# 1-Schematic_proiect.net
KiCad netlist of a schematic drawn in EasyEDA
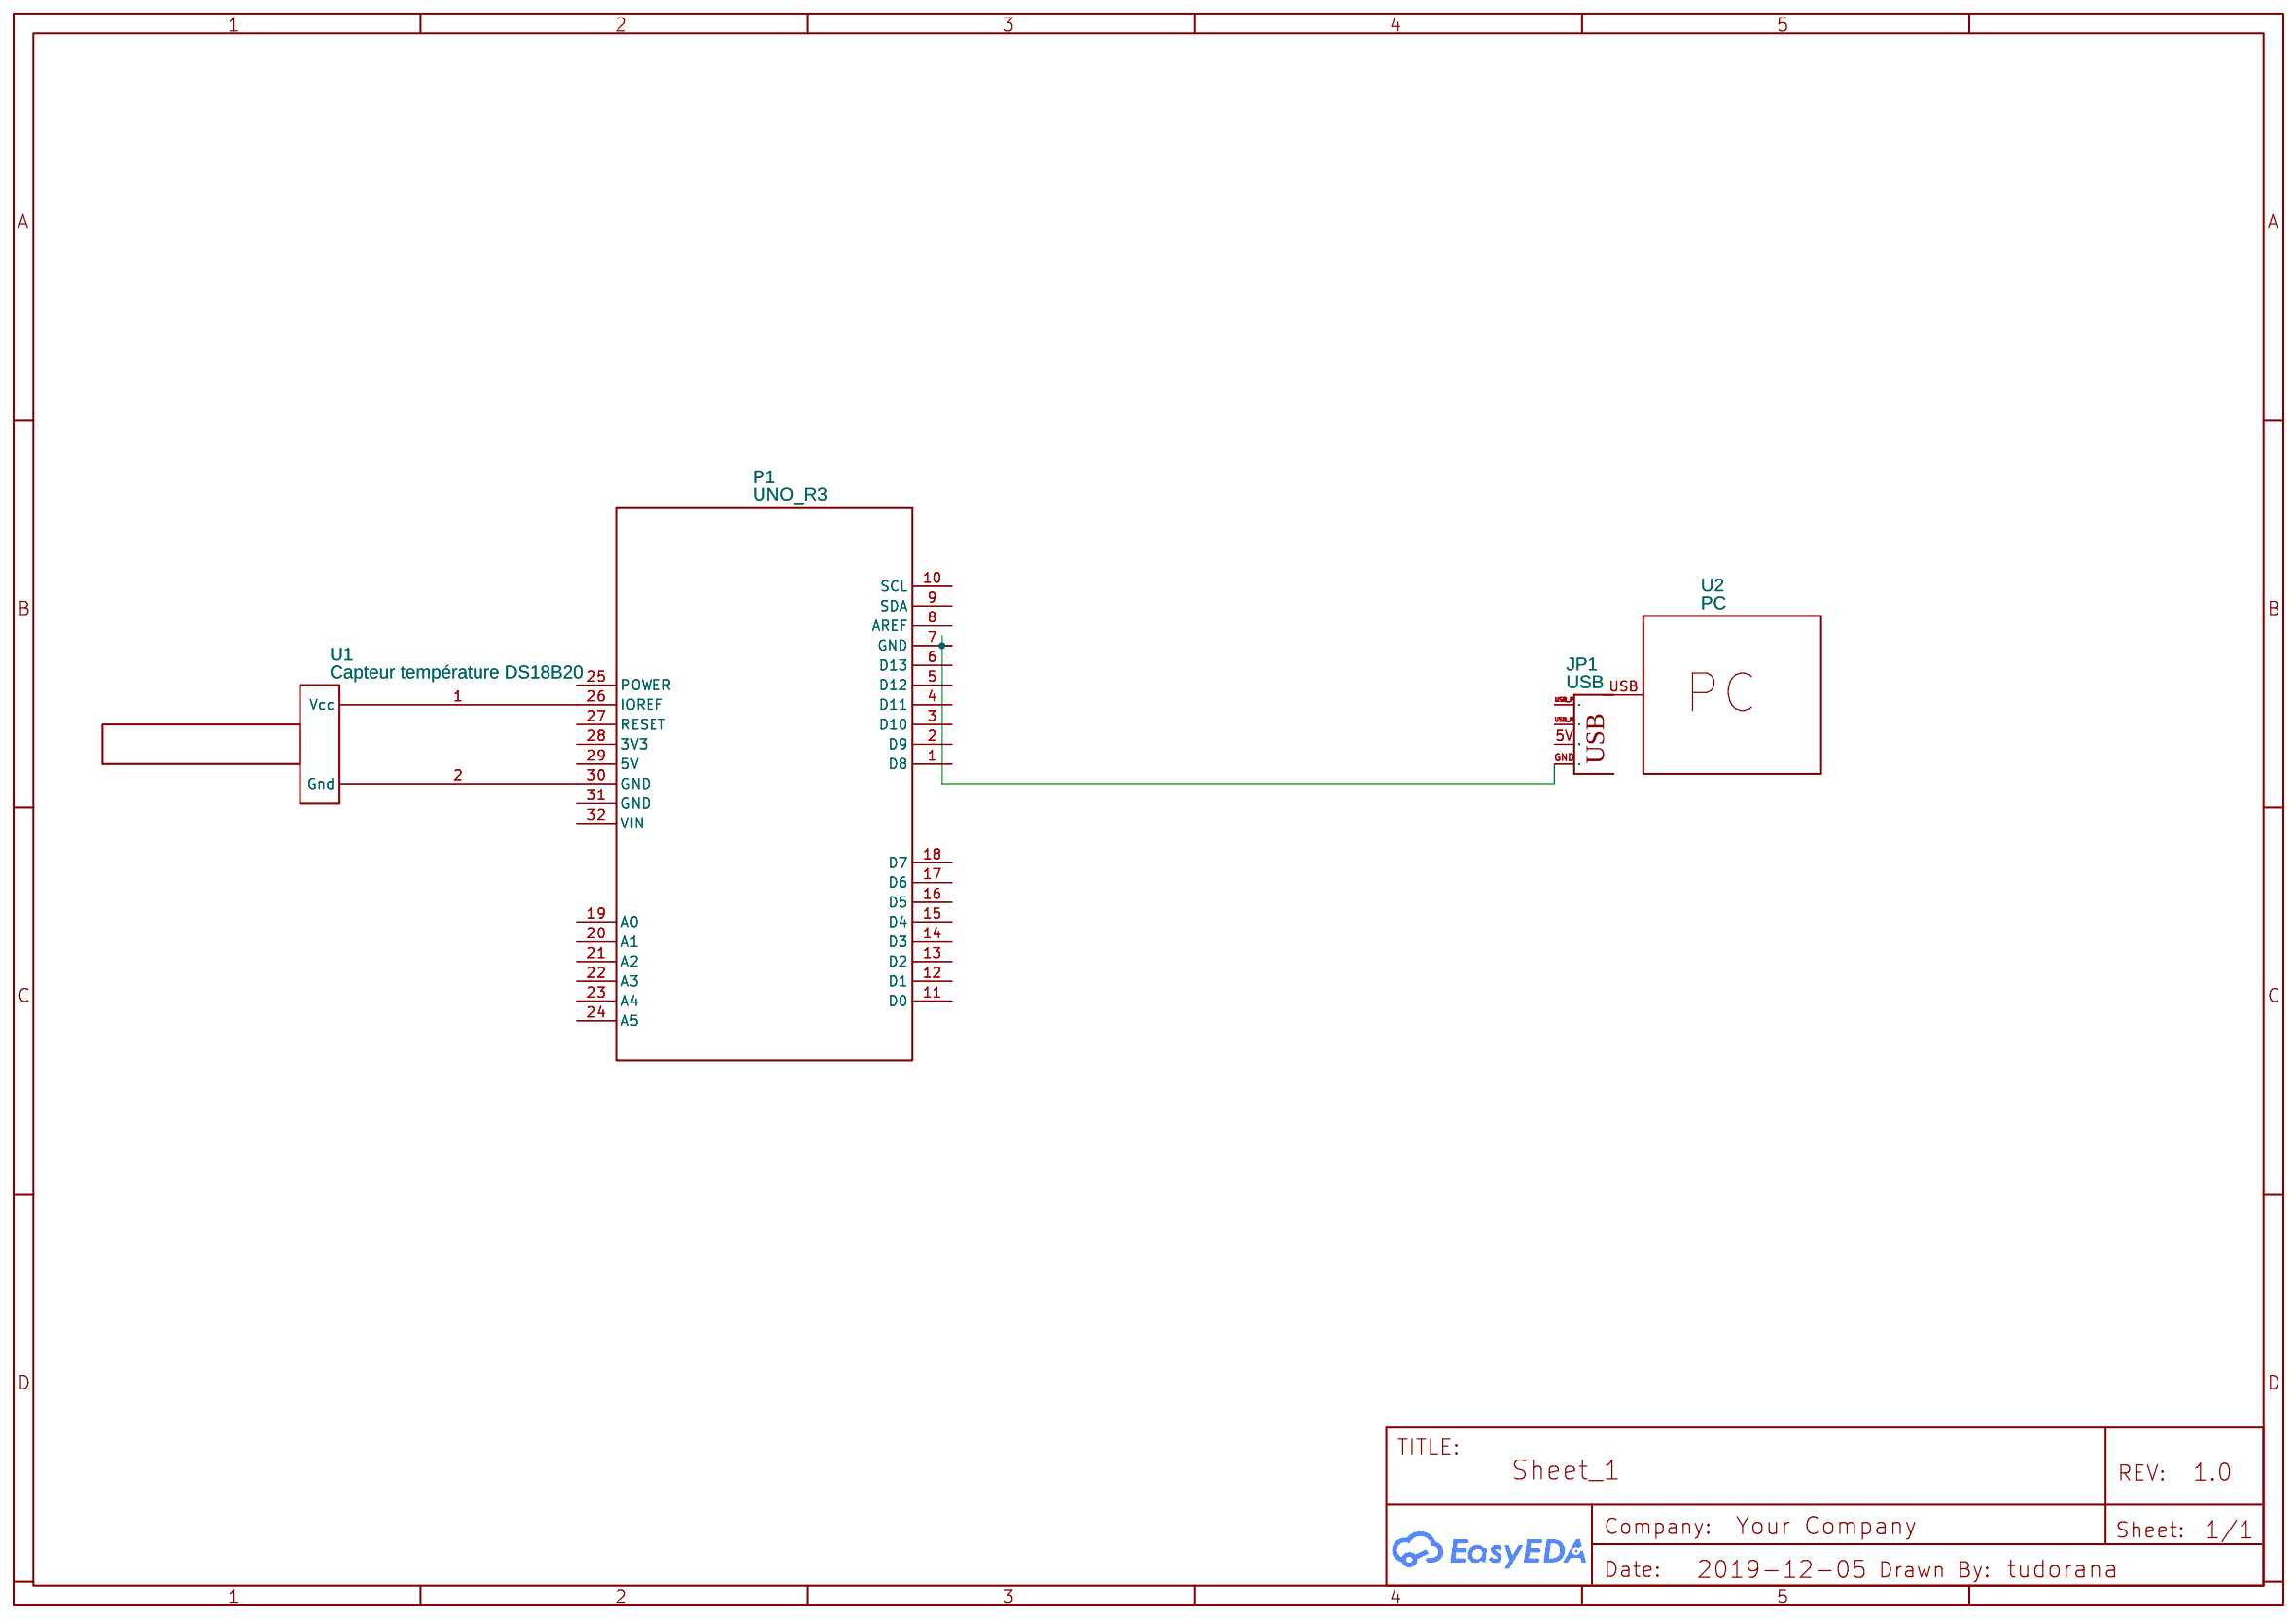
[diagram p0: schematic sheet]

(export (version "E")
  (design (tool "Eeschema 10.0.6"))
  (components
    (comp (ref "JP1") (value "USB") (libsource (lib "") (part "Unknown_780_365")))
    (comp (ref "P1") (value "UNO_R3") (libsource (lib "") (part "Unknown_380_390")))
    (comp (ref "U1") (value "Capteur température DS18B20") (libsource (lib "") (part "Unknown_265_360")))
    (comp (ref "U2") (value "PC") (libsource (lib "") (part "Unknown_905_385")))
  )
  (nets
    (net (code "1") (name "Net-(JP1-PadGND)") (class "Default")
      (node (ref "JP1") (pin "GND") (pinfunction "GND_GND") (pintype "unspecified"))
      (node (ref "P1") (pin "7") (pinfunction "GND_7") (pintype "unspecified"))
    )
    (net (code "2") (name "Net-(P1-IOREF)") (class "Default")
      (node (ref "P1") (pin "26") (pinfunction "IOREF_26") (pintype "unspecified"))
      (node (ref "U1") (pin "1") (pinfunction "Vcc_1") (pintype "passive"))
    )
    (net (code "3") (name "Net-(U1-Gnd)") (class "Default")
      (node (ref "P1") (pin "30") (pinfunction "GND_30") (pintype "unspecified"))
      (node (ref "U1") (pin "2") (pinfunction "Gnd_2") (pintype "passive"))
    )
    (net (code "4") (name "unconnected-(JP1-D+-PadUSB_P)") (class "Default")
      (node (ref "JP1") (pin "USB_P") (pinfunction "D+_USB_P") (pintype "unspecified"))
    )
    (net (code "5") (name "unconnected-(JP1-D--PadUSB_M)") (class "Default")
      (node (ref "JP1") (pin "USB_M") (pinfunction "D-_USB_M") (pintype "unspecified"))
    )
    (net (code "6") (name "unconnected-(JP1-VBUS-Pad5V)") (class "Default")
      (node (ref "JP1") (pin "5V") (pinfunction "VBUS_5V") (pintype "unspecified"))
    )
    (net (code "7") (name "unconnected-(P1-3V3-Pad28)") (class "Default")
      (node (ref "P1") (pin "28") (pinfunction "3V3_28") (pintype "unspecified"))
    )
    (net (code "8") (name "unconnected-(P1-5V-Pad29)") (class "Default")
      (node (ref "P1") (pin "29") (pinfunction "5V_29") (pintype "unspecified"))
    )
    (net (code "9") (name "unconnected-(P1-A0-Pad19)") (class "Default")
      (node (ref "P1") (pin "19") (pinfunction "A0_19") (pintype "unspecified"))
    )
    (net (code "10") (name "unconnected-(P1-A1-Pad20)") (class "Default")
      (node (ref "P1") (pin "20") (pinfunction "A1_20") (pintype "unspecified"))
    )
    (net (code "11") (name "unconnected-(P1-A2-Pad21)") (class "Default")
      (node (ref "P1") (pin "21") (pinfunction "A2_21") (pintype "unspecified"))
    )
    (net (code "12") (name "unconnected-(P1-A3-Pad22)") (class "Default")
      (node (ref "P1") (pin "22") (pinfunction "A3_22") (pintype "unspecified"))
    )
    (net (code "13") (name "unconnected-(P1-A4-Pad23)") (class "Default")
      (node (ref "P1") (pin "23") (pinfunction "A4_23") (pintype "unspecified"))
    )
    (net (code "14") (name "unconnected-(P1-A5-Pad24)") (class "Default")
      (node (ref "P1") (pin "24") (pinfunction "A5_24") (pintype "unspecified"))
    )
    (net (code "15") (name "unconnected-(P1-AREF-Pad8)") (class "Default")
      (node (ref "P1") (pin "8") (pinfunction "AREF_8") (pintype "unspecified"))
    )
    (net (code "16") (name "unconnected-(P1-D0-Pad11)") (class "Default")
      (node (ref "P1") (pin "11") (pinfunction "D0_11") (pintype "unspecified"))
    )
    (net (code "17") (name "unconnected-(P1-D1-Pad12)") (class "Default")
      (node (ref "P1") (pin "12") (pinfunction "D1_12") (pintype "unspecified"))
    )
    (net (code "18") (name "unconnected-(P1-D2-Pad13)") (class "Default")
      (node (ref "P1") (pin "13") (pinfunction "D2_13") (pintype "unspecified"))
    )
    (net (code "19") (name "unconnected-(P1-D3-Pad14)") (class "Default")
      (node (ref "P1") (pin "14") (pinfunction "D3_14") (pintype "unspecified"))
    )
    (net (code "20") (name "unconnected-(P1-D4-Pad15)") (class "Default")
      (node (ref "P1") (pin "15") (pinfunction "D4_15") (pintype "unspecified"))
    )
    (net (code "21") (name "unconnected-(P1-D5-Pad16)") (class "Default")
      (node (ref "P1") (pin "16") (pinfunction "D5_16") (pintype "unspecified"))
    )
    (net (code "22") (name "unconnected-(P1-D6-Pad17)") (class "Default")
      (node (ref "P1") (pin "17") (pinfunction "D6_17") (pintype "unspecified"))
    )
    (net (code "23") (name "unconnected-(P1-D7-Pad18)") (class "Default")
      (node (ref "P1") (pin "18") (pinfunction "D7_18") (pintype "unspecified"))
    )
    (net (code "24") (name "unconnected-(P1-D8-Pad1)") (class "Default")
      (node (ref "P1") (pin "1") (pinfunction "D8_1") (pintype "unspecified"))
    )
    (net (code "25") (name "unconnected-(P1-D9-Pad2)") (class "Default")
      (node (ref "P1") (pin "2") (pinfunction "D9_2") (pintype "unspecified"))
    )
    (net (code "26") (name "unconnected-(P1-D10-Pad3)") (class "Default")
      (node (ref "P1") (pin "3") (pinfunction "D10_3") (pintype "unspecified"))
    )
    (net (code "27") (name "unconnected-(P1-D11-Pad4)") (class "Default")
      (node (ref "P1") (pin "4") (pinfunction "D11_4") (pintype "unspecified"))
    )
    (net (code "28") (name "unconnected-(P1-D12-Pad5)") (class "Default")
      (node (ref "P1") (pin "5") (pinfunction "D12_5") (pintype "unspecified"))
    )
    (net (code "29") (name "unconnected-(P1-D13-Pad6)") (class "Default")
      (node (ref "P1") (pin "6") (pinfunction "D13_6") (pintype "unspecified"))
    )
    (net (code "30") (name "unconnected-(P1-GND-Pad31)") (class "Default")
      (node (ref "P1") (pin "31") (pinfunction "GND_31") (pintype "unspecified"))
    )
    (net (code "31") (name "unconnected-(P1-POWER-Pad25)") (class "Default")
      (node (ref "P1") (pin "25") (pinfunction "POWER_25") (pintype "unspecified"))
    )
    (net (code "32") (name "unconnected-(P1-RESET-Pad27)") (class "Default")
      (node (ref "P1") (pin "27") (pinfunction "RESET_27") (pintype "unspecified"))
    )
    (net (code "33") (name "unconnected-(P1-SCL-Pad10)") (class "Default")
      (node (ref "P1") (pin "10") (pinfunction "SCL_10") (pintype "unspecified"))
    )
    (net (code "34") (name "unconnected-(P1-SDA-Pad9)") (class "Default")
      (node (ref "P1") (pin "9") (pinfunction "SDA_9") (pintype "unspecified"))
    )
    (net (code "35") (name "unconnected-(P1-VIN-Pad32)") (class "Default")
      (node (ref "P1") (pin "32") (pinfunction "VIN_32") (pintype "unspecified"))
    )
    (net (code "36") (name "unconnected-(U2-1-PadUSB)") (class "Default")
      (node (ref "U2") (pin "USB") (pinfunction "1_USB") (pintype "unspecified"))
    )
  )
)
